# ADC_8CH.net
KiCad netlist of a schematic drawn in Altium Designer
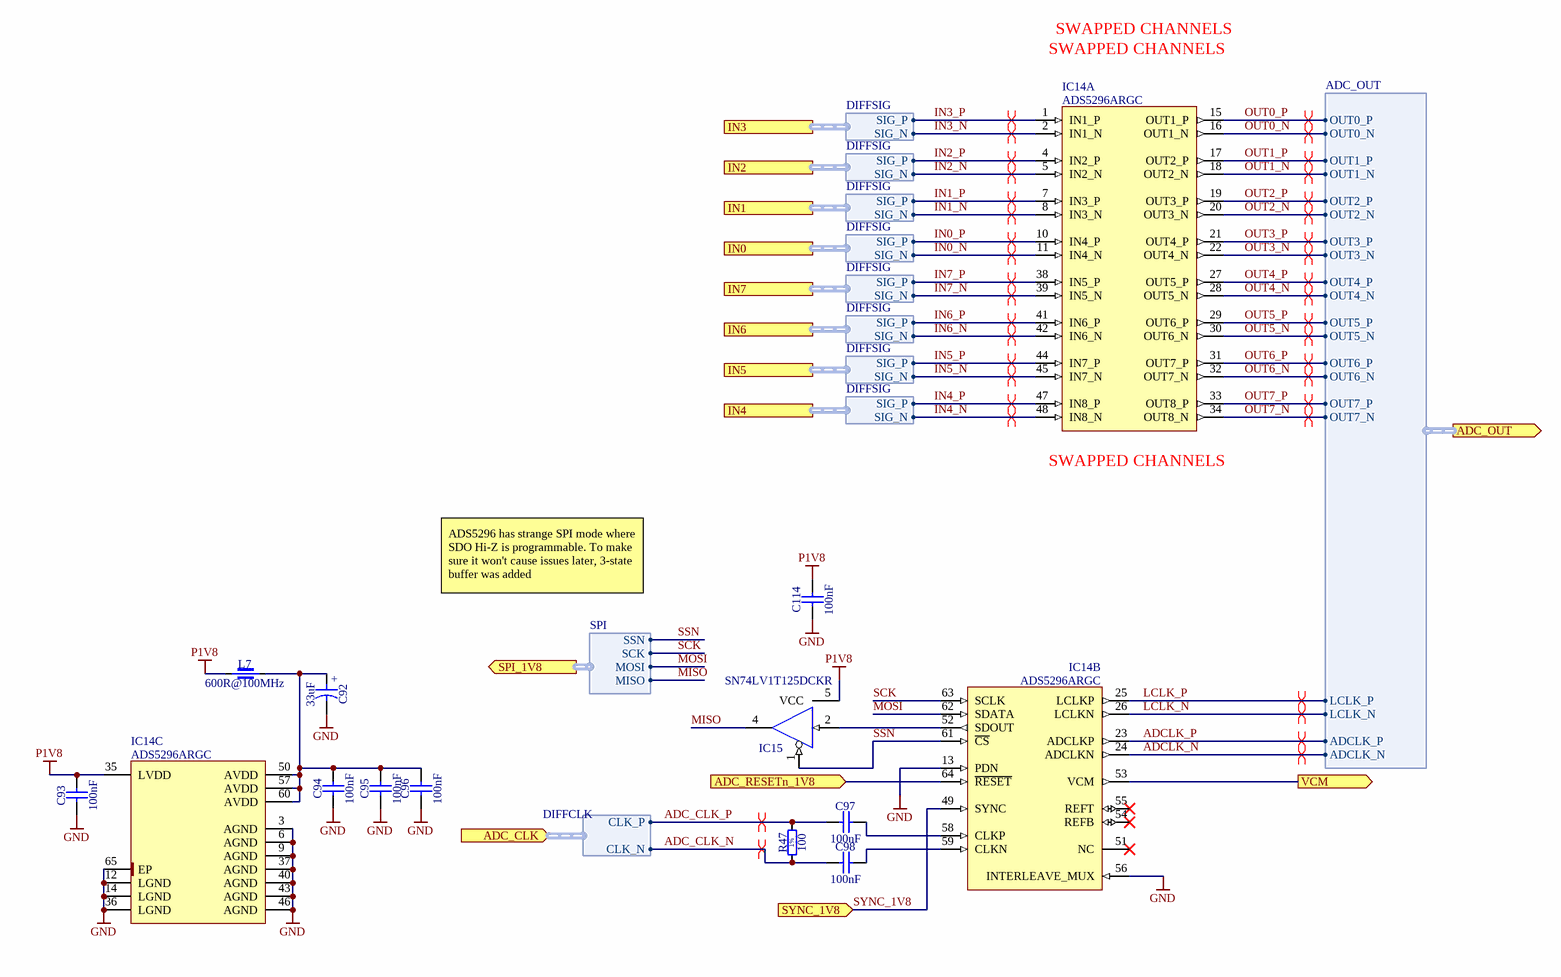
[diagram p0: ADC_8CH.SchDoc]

(export (version "E")
  (design (tool "Eeschema 10.0.6"))
  (components
    (comp (ref "C92")
      (value "33uF")
      (footprint "CAPMP3216X180N")
      (description "Polarised capacitor")
      (fields
        (field (name "PART NUMBER") "CTE3216-18_33UF_4V_10%")
        (field (name "VOLTAGE") "4V")
        (field (name "AUTHOR") "CERN DEM JLC")
      )
      (libsource (lib "Capacitors") (part "Capacitor - polarized"))
    )
    (comp (ref "C93")
      (value "100nF")
      (footprint "CAPC0603X33N")
      (description "Non-polarised capacitor")
      (fields
        (field (name "PART NUMBER") "CC0201_100NF_6.3V_10%_X5R")
        (field (name "VOLTAGE") "6.3V")
        (field (name "AUTHOR") "CERN DEM JLC")
      )
      (libsource (lib "Capacitors") (part "Capacitor - non polarized"))
    )
    (comp (ref "C94")
      (value "100nF")
      (footprint "CAPC0603X33N")
      (description "Non-polarised capacitor")
      (fields
        (field (name "PART NUMBER") "CC0201_100NF_6.3V_10%_X5R")
        (field (name "VOLTAGE") "6.3V")
        (field (name "AUTHOR") "CERN DEM JLC")
      )
      (libsource (lib "Capacitors") (part "Capacitor - non polarized"))
    )
    (comp (ref "C95")
      (value "100nF")
      (footprint "CAPC0603X33N")
      (description "Non-polarised capacitor")
      (fields
        (field (name "PART NUMBER") "CC0201_100NF_6.3V_10%_X5R")
        (field (name "VOLTAGE") "6.3V")
        (field (name "AUTHOR") "CERN DEM JLC")
      )
      (libsource (lib "Capacitors") (part "Capacitor - non polarized"))
    )
    (comp (ref "C96")
      (value "100nF")
      (footprint "CAPC0603X33N")
      (description "Non-polarised capacitor")
      (fields
        (field (name "PART NUMBER") "CC0201_100NF_6.3V_10%_X5R")
        (field (name "VOLTAGE") "6.3V")
        (field (name "AUTHOR") "CERN DEM JLC")
      )
      (libsource (lib "Capacitors") (part "Capacitor - non polarized"))
    )
    (comp (ref "C97")
      (value "100nF")
      (footprint "CAPC0603X33N")
      (description "Non-polarised capacitor")
      (fields
        (field (name "PART NUMBER") "CC0201_100NF_6.3V_10%_X5R")
        (field (name "VOLTAGE") "6.3V")
        (field (name "AUTHOR") "CERN DEM JLC")
      )
      (libsource (lib "Capacitors") (part "Capacitor - non polarized"))
    )
    (comp (ref "C98")
      (value "100nF")
      (footprint "CAPC0603X33N")
      (description "Non-polarised capacitor")
      (fields
        (field (name "PART NUMBER") "CC0201_100NF_6.3V_10%_X5R")
        (field (name "VOLTAGE") "6.3V")
        (field (name "AUTHOR") "CERN DEM JLC")
      )
      (libsource (lib "Capacitors") (part "Capacitor - non polarized"))
    )
    (comp (ref "C114")
      (value "100nF")
      (footprint "CAPC0603X33N")
      (description "Non-polarised capacitor")
      (fields
        (field (name "PART NUMBER") "CC0201_100NF_6.3V_10%_X5R")
        (field (name "VOLTAGE") "6.3V")
        (field (name "AUTHOR") "CERN DEM JLC")
      )
      (libsource (lib "Capacitors") (part "Capacitor - non polarized"))
    )
    (comp (ref "IC14")
      (value "ADS5296ARGC")
      (footprint "QFN50P900X900X100-65N-S735")
      (description "10-Bit, 200-MSPS, 4-Channel and 12-Bit, 80-MSPS, 8-Channel ADC")
      (fields (field (name "MANUFACTURER") "TEXAS INSTRUMENTS") (field (name "AUTHOR") "CERN DEM MR"))
      (libsource (lib "") (part "ADS5296_1"))
    )
    (comp (ref "IC15")
      (value "SN74LV1T125DCKR")
      (footprint "SOT65P210X110-5N")
      (description "Single Power Supply Single Buffer Gate with 3-State Output CMOS Logic Level Shifter")
      (fields (field (name "MANUFACTURER") "TEXAS INSTRUMENTS") (field (name "AUTHOR") "CERN DEM JLC"))
      (libsource (lib "ICs And Semiconductors") (part "741T125"))
    )
    (comp (ref "L7")
      (value "600R@100MHz")
      (footprint "INDC1005X55N")
      (fields
        (field (name "PART NUMBER") "IND0402_MURATA_BLM15HD601SN1")
        (field (name "POWER") "300mA")
        (field (name "TOLERANCE") "±25%")
        (field (name "AUTHOR") "CERN DEM JLC")
      )
      (libsource (lib "Inductors & Transformers") (part "Ferrite Bead"))
    )
    (comp (ref "R47")
      (value "100")
      (footprint "RESC0603X28N")
      (description "Resistor - 1%")
      (fields
        (field (name "PART NUMBER") "R0201_100R_1%_0.05W_200PPM")
        (field (name "POWER") "0.05W")
        (field (name "AUTHOR") "CERN DEM JLC")
      )
      (libsource (lib "Resistors") (part "Resistor - 1%"))
    )
  )
  (nets
    (net (code "5") (name "/ADCLK_N") (class "Default")
      (node (ref "IC14") (pin "24") (pinfunction "ADCLKN_24") (pintype "output"))
    )
    (net (code "6") (name "/ADCLK_P") (class "Default")
      (node (ref "IC14") (pin "23") (pinfunction "ADCLKP_23") (pintype "output"))
    )
    (net (code "7") (name "/ADC_CLK_N") (class "Default")
      (node (ref "C98") (pin "1") (pinfunction "1_1") (pintype "passive"))
      (node (ref "R47") (pin "1") (pinfunction "1_1") (pintype "passive"))
    )
    (net (code "8") (name "/ADC_CLK_P") (class "Default")
      (node (ref "C97") (pin "1") (pinfunction "1_1") (pintype "passive"))
      (node (ref "R47") (pin "2") (pinfunction "2_2") (pintype "passive"))
    )
    (net (code "9") (name "/ADC_RESETn_1V8") (class "Default")
      (node (ref "IC14") (pin "64") (pinfunction "~{RESET}_64") (pintype "input"))
    )
    (net (code "10") (name "/IN0_N") (class "Default")
      (node (ref "IC14") (pin "11") (pinfunction "IN4_N_11") (pintype "input"))
    )
    (net (code "11") (name "/IN0_P") (class "Default")
      (node (ref "IC14") (pin "10") (pinfunction "IN4_P_10") (pintype "input"))
    )
    (net (code "12") (name "/IN1_N") (class "Default")
      (node (ref "IC14") (pin "8") (pinfunction "IN3_N_8") (pintype "input"))
    )
    (net (code "13") (name "/IN1_P") (class "Default")
      (node (ref "IC14") (pin "7") (pinfunction "IN3_P_7") (pintype "input"))
    )
    (net (code "14") (name "/IN2_N") (class "Default")
      (node (ref "IC14") (pin "5") (pinfunction "IN2_N_5") (pintype "input"))
    )
    (net (code "15") (name "/IN2_P") (class "Default")
      (node (ref "IC14") (pin "4") (pinfunction "IN2_P_4") (pintype "input"))
    )
    (net (code "16") (name "/IN3_N") (class "Default")
      (node (ref "IC14") (pin "2") (pinfunction "IN1_N_2") (pintype "input"))
    )
    (net (code "17") (name "/IN3_P") (class "Default")
      (node (ref "IC14") (pin "1") (pinfunction "IN1_P_1") (pintype "input"))
    )
    (net (code "18") (name "/IN4_N") (class "Default")
      (node (ref "IC14") (pin "48") (pinfunction "IN8_N_48") (pintype "input"))
    )
    (net (code "19") (name "/IN4_P") (class "Default")
      (node (ref "IC14") (pin "47") (pinfunction "IN8_P_47") (pintype "input"))
    )
    (net (code "20") (name "/IN5_N") (class "Default")
      (node (ref "IC14") (pin "45") (pinfunction "IN7_N_45") (pintype "input"))
    )
    (net (code "21") (name "/IN5_P") (class "Default")
      (node (ref "IC14") (pin "44") (pinfunction "IN7_P_44") (pintype "input"))
    )
    (net (code "22") (name "/IN6_N") (class "Default")
      (node (ref "IC14") (pin "42") (pinfunction "IN6_N_42") (pintype "input"))
    )
    (net (code "23") (name "/IN6_P") (class "Default")
      (node (ref "IC14") (pin "41") (pinfunction "IN6_P_41") (pintype "input"))
    )
    (net (code "24") (name "/IN7_N") (class "Default")
      (node (ref "IC14") (pin "39") (pinfunction "IN5_N_39") (pintype "input"))
    )
    (net (code "25") (name "/IN7_P") (class "Default")
      (node (ref "IC14") (pin "38") (pinfunction "IN5_P_38") (pintype "input"))
    )
    (net (code "26") (name "/LCLK_N") (class "Default")
      (node (ref "IC14") (pin "26") (pinfunction "LCLKN_26") (pintype "output"))
    )
    (net (code "27") (name "/LCLK_P") (class "Default")
      (node (ref "IC14") (pin "25") (pinfunction "LCLKP_25") (pintype "output"))
    )
    (net (code "28") (name "/MISO") (class "Default")
      (node (ref "IC15") (pin "4") (pinfunction "OUT_4") (pintype "tri_state"))
    )
    (net (code "29") (name "/MOSI") (class "Default")
      (node (ref "IC14") (pin "62") (pinfunction "SDATA_62") (pintype "input"))
    )
    (net (code "30") (name "/OUT0_N") (class "Default")
      (node (ref "IC14") (pin "16") (pinfunction "OUT1_N_16") (pintype "output"))
    )
    (net (code "31") (name "/OUT0_P") (class "Default")
      (node (ref "IC14") (pin "15") (pinfunction "OUT1_P_15") (pintype "output"))
    )
    (net (code "32") (name "/OUT1_N") (class "Default")
      (node (ref "IC14") (pin "18") (pinfunction "OUT2_N_18") (pintype "output"))
    )
    (net (code "33") (name "/OUT1_P") (class "Default")
      (node (ref "IC14") (pin "17") (pinfunction "OUT2_P_17") (pintype "output"))
    )
    (net (code "34") (name "/OUT2_N") (class "Default")
      (node (ref "IC14") (pin "20") (pinfunction "OUT3_N_20") (pintype "output"))
    )
    (net (code "35") (name "/OUT2_P") (class "Default")
      (node (ref "IC14") (pin "19") (pinfunction "OUT3_P_19") (pintype "output"))
    )
    (net (code "36") (name "/OUT3_N") (class "Default")
      (node (ref "IC14") (pin "22") (pinfunction "OUT4_N_22") (pintype "output"))
    )
    (net (code "37") (name "/OUT3_P") (class "Default")
      (node (ref "IC14") (pin "21") (pinfunction "OUT4_P_21") (pintype "output"))
    )
    (net (code "38") (name "/OUT4_N") (class "Default")
      (node (ref "IC14") (pin "28") (pinfunction "OUT5_N_28") (pintype "output"))
    )
    (net (code "39") (name "/OUT4_P") (class "Default")
      (node (ref "IC14") (pin "27") (pinfunction "OUT5_P_27") (pintype "output"))
    )
    (net (code "40") (name "/OUT5_N") (class "Default")
      (node (ref "IC14") (pin "30") (pinfunction "OUT6_N_30") (pintype "output"))
    )
    (net (code "41") (name "/OUT5_P") (class "Default")
      (node (ref "IC14") (pin "29") (pinfunction "OUT6_P_29") (pintype "output"))
    )
    (net (code "42") (name "/OUT6_N") (class "Default")
      (node (ref "IC14") (pin "32") (pinfunction "OUT7_N_32") (pintype "output"))
    )
    (net (code "43") (name "/OUT6_P") (class "Default")
      (node (ref "IC14") (pin "31") (pinfunction "OUT7_P_31") (pintype "output"))
    )
    (net (code "44") (name "/OUT7_N") (class "Default")
      (node (ref "IC14") (pin "34") (pinfunction "OUT8_N_34") (pintype "output"))
    )
    (net (code "45") (name "/OUT7_P") (class "Default")
      (node (ref "IC14") (pin "33") (pinfunction "OUT8_P_33") (pintype "output"))
    )
    (net (code "46") (name "/SCK") (class "Default")
      (node (ref "IC14") (pin "63") (pinfunction "SCLK_63") (pintype "input"))
    )
    (net (code "47") (name "/SSN") (class "Default")
      (node (ref "IC14") (pin "61") (pinfunction "~{CS}_61") (pintype "input"))
      (node (ref "IC15") (pin "1") (pinfunction "~{G}_1") (pintype "input"))
    )
    (net (code "48") (name "/SYNC_1V8") (class "Default")
      (node (ref "IC14") (pin "49") (pinfunction "SYNC_49") (pintype "input"))
    )
    (net (code "49") (name "/VCM") (class "Default")
      (node (ref "IC14") (pin "53") (pinfunction "VCM_53") (pintype "output"))
    )
    (net (code "54") (name "GND") (class "Default")
      (node (ref "C114") (pin "1") (pinfunction "1_1") (pintype "passive"))
      (node (ref "C92") (pin "2") (pinfunction "2_2") (pintype "passive"))
      (node (ref "C93") (pin "1") (pinfunction "1_1") (pintype "passive"))
      (node (ref "C94") (pin "1") (pinfunction "1_1") (pintype "passive"))
      (node (ref "C95") (pin "1") (pinfunction "1_1") (pintype "passive"))
      (node (ref "C96") (pin "1") (pinfunction "1_1") (pintype "passive"))
      (node (ref "IC14") (pin "12") (pinfunction "LGND_12") (pintype "power_in"))
      (node (ref "IC14") (pin "13") (pinfunction "PDN_13") (pintype "input"))
      (node (ref "IC14") (pin "14") (pinfunction "LGND_14") (pintype "power_in"))
      (node (ref "IC14") (pin "3") (pinfunction "AGND_3") (pintype "power_in"))
      (node (ref "IC14") (pin "36") (pinfunction "LGND_36") (pintype "power_in"))
      (node (ref "IC14") (pin "37") (pinfunction "AGND_37") (pintype "power_in"))
      (node (ref "IC14") (pin "40") (pinfunction "AGND_40") (pintype "power_in"))
      (node (ref "IC14") (pin "43") (pinfunction "AGND_43") (pintype "power_in"))
      (node (ref "IC14") (pin "46") (pinfunction "AGND_46") (pintype "power_in"))
      (node (ref "IC14") (pin "56") (pinfunction "INTERLEAVE_MUX_56") (pintype "input"))
      (node (ref "IC14") (pin "6") (pinfunction "AGND_6") (pintype "power_in"))
      (node (ref "IC14") (pin "65") (pinfunction "EP_65") (pintype "power_in"))
      (node (ref "IC14") (pin "9") (pinfunction "AGND_9") (pintype "power_in"))
      (node (ref "IC15") (pin "3") (pinfunction "GND_3") (pintype "power_in"))
    )
    (net (code "55") (name "Net-(C92-Pad1)") (class "Default")
      (node (ref "C92") (pin "1") (pinfunction "1_1") (pintype "passive"))
      (node (ref "C94") (pin "2") (pinfunction "2_2") (pintype "passive"))
      (node (ref "C95") (pin "2") (pinfunction "2_2") (pintype "passive"))
      (node (ref "C96") (pin "2") (pinfunction "2_2") (pintype "passive"))
      (node (ref "IC14") (pin "50") (pinfunction "AVDD_50") (pintype "power_in"))
      (node (ref "IC14") (pin "57") (pinfunction "AVDD_57") (pintype "power_in"))
      (node (ref "IC14") (pin "60") (pinfunction "AVDD_60") (pintype "power_in"))
      (node (ref "L7") (pin "2") (pinfunction "2_2") (pintype "passive"))
    )
    (net (code "56") (name "Net-(IC14B-CLKN)") (class "Default")
      (node (ref "C98") (pin "2") (pinfunction "2_2") (pintype "passive"))
      (node (ref "IC14") (pin "59") (pinfunction "CLKN_59") (pintype "input"))
    )
    (net (code "57") (name "Net-(IC14B-CLKP)") (class "Default")
      (node (ref "C97") (pin "2") (pinfunction "2_2") (pintype "passive"))
      (node (ref "IC14") (pin "58") (pinfunction "CLKP_58") (pintype "input"))
    )
    (net (code "58") (name "Net-(IC14B-SDOUT)") (class "Default")
      (node (ref "IC14") (pin "52") (pinfunction "SDOUT_52") (pintype "output"))
      (node (ref "IC15") (pin "2") (pinfunction "IN_2") (pintype "input"))
    )
    (net (code "59") (name "P1V8") (class "Default")
      (node (ref "C114") (pin "2") (pinfunction "2_2") (pintype "passive"))
      (node (ref "C93") (pin "2") (pinfunction "2_2") (pintype "passive"))
      (node (ref "IC14") (pin "35") (pinfunction "LVDD_35") (pintype "power_in"))
      (node (ref "IC15") (pin "5") (pinfunction "VCC_5") (pintype "power_in"))
      (node (ref "L7") (pin "1") (pinfunction "1_1") (pintype "passive"))
    )
    (net (code "60") (name "unconnected-(IC14B-NC-Pad51)") (class "Default")
      (node (ref "IC14") (pin "51") (pinfunction "NC_51") (pintype "passive+no_connect"))
    )
    (net (code "61") (name "unconnected-(IC14B-REFB-Pad54)") (class "Default")
      (node (ref "IC14") (pin "54") (pinfunction "REFB_54") (pintype "bidirectional+no_connect"))
    )
    (net (code "62") (name "unconnected-(IC14B-REFT-Pad55)") (class "Default")
      (node (ref "IC14") (pin "55") (pinfunction "REFT_55") (pintype "bidirectional+no_connect"))
    )
  )
)
